# quadcopter.net
KiCad netlist of a schematic drawn in EAGLE
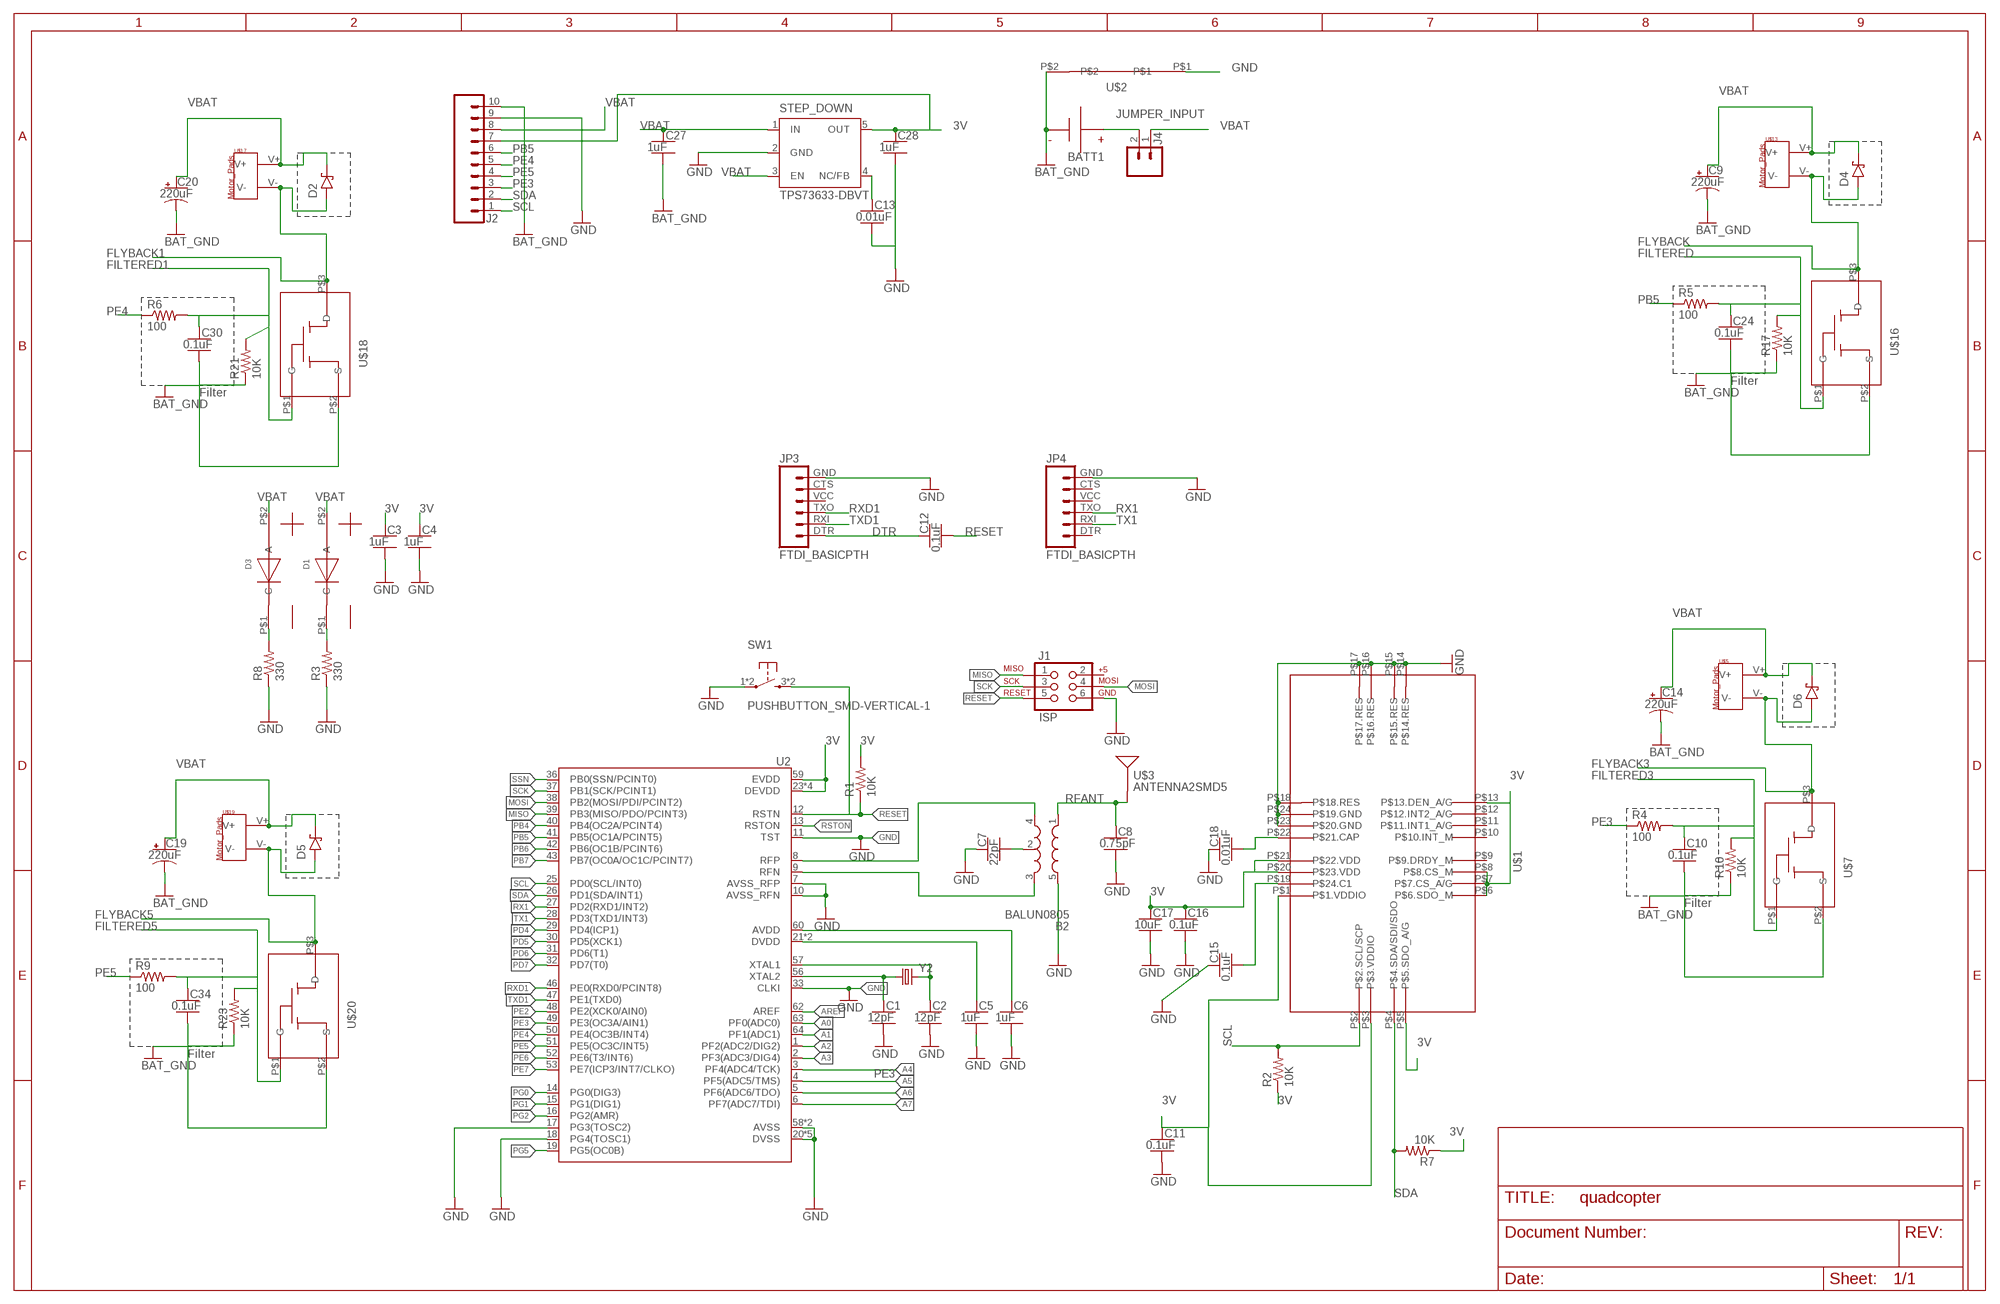
[diagram p0: schematic, sheet 1]

(export (version "E")
  (design (tool "Eeschema 10.0.6"))
  (components
    (comp (ref "B2")
      (value "BALUN0805")
      (footprint "eagle-import:BALUN")
      (fields (field (name "MFR") "Wurth Electronics Inc") (field (name "MPN") "748421245"))
      (libsource (lib "eagle-import") (part "BALUN0805"))
    )
    (comp (ref "BATT1")
      (value "BATTERY-HUBSAN-W/HOLDER")
      (footprint "eagle-import:BATTERY-W_HOLDER-380MAH-HUBSAN")
      (fields
        (field (name "MFR") "HUBSAN")
        (field (name "MPN") "X4-H107C-8-in-1")
        (field (name "CREATOR") "Swanson")
      )
      (libsource (lib "eagle-import") (part "BATTERY-HUBSAN-W/HOLDER"))
    )
    (comp (ref "C1")
      (value "12pF")
      (footprint "eagle-import:CAPC2012X140_HS")
      (fields
        (field (name "MFR") "Murata Electronics North America")
        (field (name "MPN") "GRM21A5C2E120JW01D")
      )
      (libsource (lib "eagle-import") (part "CAPACITOR-NP_SMD-2012-0805_CERAMIC-12PF"))
    )
    (comp (ref "C2")
      (value "12pF")
      (footprint "eagle-import:CAPC2012X140_HS")
      (fields
        (field (name "MFR") "Murata Electronics North America")
        (field (name "MPN") "GRM21A5C2E120JW01D")
      )
      (libsource (lib "eagle-import") (part "CAPACITOR-NP_SMD-2012-0805_CERAMIC-12PF"))
    )
    (comp (ref "C3")
      (value "1uF")
      (footprint "eagle-import:CAPC2012X140_HS")
      (fields
        (field (name "MFR") "Murata Electronics North America")
        (field (name "MPN") "GRM21BR71H105KA12L")
      )
      (libsource (lib "eagle-import") (part "CAPACITOR-NP_SMD-2012-0805_CERAMIC-1UF"))
    )
    (comp (ref "C4")
      (value "1uF")
      (footprint "eagle-import:CAPC2012X140_HS")
      (fields
        (field (name "MFR") "Murata Electronics North America")
        (field (name "MPN") "GRM21BR71H105KA12L")
      )
      (libsource (lib "eagle-import") (part "CAPACITOR-NP_SMD-2012-0805_CERAMIC-1UF"))
    )
    (comp (ref "C5")
      (value "1uF")
      (footprint "eagle-import:CAPC2012X140_HS")
      (fields
        (field (name "MFR") "Murata Electronics North America")
        (field (name "MPN") "GRM21BR71H105KA12L")
      )
      (libsource (lib "eagle-import") (part "CAPACITOR-NP_SMD-2012-0805_CERAMIC-1UF"))
    )
    (comp (ref "C6")
      (value "1uF")
      (footprint "eagle-import:CAPC2012X140_HS")
      (fields
        (field (name "MFR") "Murata Electronics North America")
        (field (name "MPN") "GRM21BR71H105KA12L")
      )
      (libsource (lib "eagle-import") (part "CAPACITOR-NP_SMD-2012-0805_CERAMIC-1UF"))
    )
    (comp (ref "C7")
      (value "22pF")
      (footprint "eagle-import:CAPC2012X140_HS")
      (fields
        (field (name "MFR") "Murata Electronics North America")
        (field (name "MPN") "GRM21A5C2E220JW01D")
      )
      (libsource (lib "eagle-import") (part "CAPACITOR-NP_SMD-2012-0805_CERAMIC-22PF"))
    )
    (comp (ref "C8")
      (value "0.75pF")
      (footprint "eagle-import:CAPC2012X140_HS")
      (fields
        (field (name "MFR") "Murata Electronics North America")
        (field (name "MPN") "GQM2195C2AR75CB01D")
      )
      (libsource (lib "eagle-import") (part "CAPACITOR-NP_SMD-2012-0805_CERAMIC-0.75PF"))
    )
    (comp (ref "C9")
      (value "220uF")
      (footprint "eagle-import:CAPMP7343X310_HS")
      (fields (field (name "MFR") "AVX Corporation") (field (name "MPN") "TAJD227K006RNJ"))
      (libsource (lib "eagle-import") (part "CAPACITOR-POL_SMD-7043-D_TANTALUM-220UF"))
    )
    (comp (ref "C10")
      (value "0.1uF")
      (footprint "eagle-import:CAPC2012X140_HS")
      (fields
        (field (name "MFR") "Murata Electronics North America")
        (field (name "MPN") "GRM21BR71H104KA01L")
      )
      (libsource (lib "eagle-import") (part "CAPACITOR-NP_SMD-2012-0805_CERAMIC-0.1UF"))
    )
    (comp (ref "C11")
      (value "0.1uF")
      (footprint "eagle-import:CAPC2012X140_HS")
      (fields
        (field (name "MFR") "Murata Electronics North America")
        (field (name "MPN") "GRM21BR71H104KA01L")
      )
      (libsource (lib "eagle-import") (part "CAPACITOR-NP_SMD-2012-0805_CERAMIC-0.1UF"))
    )
    (comp (ref "C12")
      (value "0.1uF")
      (footprint "eagle-import:CAPC2012X140_HS")
      (fields
        (field (name "MFR") "Murata Electronics North America")
        (field (name "MPN") "GRM21BR71H104KA01L")
      )
      (libsource (lib "eagle-import") (part "CAPACITOR-NP_SMD-2012-0805_CERAMIC-0.1UF"))
    )
    (comp (ref "C13")
      (value "0.01uF")
      (footprint "eagle-import:CAPC2012X140_HS")
      (fields
        (field (name "MFR") "Murata Electronics North America")
        (field (name "MPN") "GRM2195C1H103FA01D")
      )
      (libsource (lib "eagle-import") (part "CAPACITOR-NP_SMD-2012-0805_CERAMIC-0.01UF"))
    )
    (comp (ref "C14")
      (value "220uF")
      (footprint "eagle-import:CAPMP7343X310_HS")
      (fields (field (name "MFR") "AVX Corporation") (field (name "MPN") "TAJD227K006RNJ"))
      (libsource (lib "eagle-import") (part "CAPACITOR-POL_SMD-7043-D_TANTALUM-220UF"))
    )
    (comp (ref "C15")
      (value "0.1uF")
      (footprint "eagle-import:CAPC2012X140_HS")
      (fields
        (field (name "MFR") "Murata Electronics North America")
        (field (name "MPN") "GRM21BR71H104KA01L")
      )
      (libsource (lib "eagle-import") (part "CAPACITOR-NP_SMD-2012-0805_CERAMIC-0.1UF"))
    )
    (comp (ref "C16")
      (value "0.1uF")
      (footprint "eagle-import:CAPC2012X140_HS")
      (fields
        (field (name "MFR") "Murata Electronics North America")
        (field (name "MPN") "GRM21BR71H104KA01L")
      )
      (libsource (lib "eagle-import") (part "CAPACITOR-NP_SMD-2012-0805_CERAMIC-0.1UF"))
    )
    (comp (ref "C17")
      (value "10uF")
      (footprint "eagle-import:CAPC2012X140_HS")
      (fields
        (field (name "MFR") "Murata Electronics North America")
        (field (name "MPN") "GRM21BR61E106KA73L")
      )
      (libsource (lib "eagle-import") (part "CAPACITOR-NP_SMD-2012-0805_CERAMIC-10UF"))
    )
    (comp (ref "C18")
      (value "0.01uF")
      (footprint "eagle-import:CAPC2012X140_HS")
      (fields
        (field (name "MFR") "Murata Electronics North America")
        (field (name "MPN") "GRM2195C1H103FA01D")
      )
      (libsource (lib "eagle-import") (part "CAPACITOR-NP_SMD-2012-0805_CERAMIC-0.01UF"))
    )
    (comp (ref "C19")
      (value "220uF")
      (footprint "eagle-import:CAPMP7343X310_HS")
      (fields (field (name "MFR") "AVX Corporation") (field (name "MPN") "TAJD227K006RNJ"))
      (libsource (lib "eagle-import") (part "CAPACITOR-POL_SMD-7043-D_TANTALUM-220UF"))
    )
    (comp (ref "C20")
      (value "220uF")
      (footprint "eagle-import:CAPMP7343X310_HS")
      (fields (field (name "MFR") "AVX Corporation") (field (name "MPN") "TAJD227K006RNJ"))
      (libsource (lib "eagle-import") (part "CAPACITOR-POL_SMD-7043-D_TANTALUM-220UF"))
    )
    (comp (ref "C24")
      (value "0.1uF")
      (footprint "eagle-import:CAPC2012X140_HS")
      (fields
        (field (name "MFR") "Murata Electronics North America")
        (field (name "MPN") "GRM21BR71H104KA01L")
      )
      (libsource (lib "eagle-import") (part "CAPACITOR-NP_SMD-2012-0805_CERAMIC-0.1UF"))
    )
    (comp (ref "C27")
      (value "1uF")
      (footprint "eagle-import:CAPC2012X140_HS")
      (fields
        (field (name "MFR") "Murata Electronics North America")
        (field (name "MPN") "GRM21BR71H105KA12L")
      )
      (libsource (lib "eagle-import") (part "CAPACITOR-NP_SMD-2012-0805_CERAMIC-1UF"))
    )
    (comp (ref "C28")
      (value "1uF")
      (footprint "eagle-import:CAPC2012X140_HS")
      (fields
        (field (name "MFR") "Murata Electronics North America")
        (field (name "MPN") "GRM21BR71H105KA12L")
      )
      (libsource (lib "eagle-import") (part "CAPACITOR-NP_SMD-2012-0805_CERAMIC-1UF"))
    )
    (comp (ref "C30")
      (value "0.1uF")
      (footprint "eagle-import:CAPC2012X140_HS")
      (fields
        (field (name "MFR") "Murata Electronics North America")
        (field (name "MPN") "GRM21BR71H104KA01L")
      )
      (libsource (lib "eagle-import") (part "CAPACITOR-NP_SMD-2012-0805_CERAMIC-0.1UF"))
    )
    (comp (ref "C34")
      (value "0.1uF")
      (footprint "eagle-import:CAPC2012X140_HS")
      (fields
        (field (name "MFR") "Murata Electronics North America")
        (field (name "MPN") "GRM21BR71H104KA01L")
      )
      (libsource (lib "eagle-import") (part "CAPACITOR-NP_SMD-2012-0805_CERAMIC-0.1UF"))
    )
    (comp (ref "D1")
      (value "LED-RED")
      (footprint "eagle-import:RED_LED")
      (fields
        (field (name "MFR") "Lite-On Inc ")
        (field (name "MPN") "LTST-C170EKT ")
        (field (name "CREATOR") "Michael Bagherpour")
        (field (name "REVIEWER") "group 4")
      )
      (libsource (lib "eagle-import") (part "LED-RED"))
    )
    (comp (ref "D2")
      (value "DIODE-SCHOTTKY_SMD-SOD123")
      (footprint "eagle-import:SOD3716X135_HS")
      (libsource (lib "eagle-import") (part "DIODE-SCHOTTKY_SMD-SOD123"))
    )
    (comp (ref "D3")
      (value "LED-RED")
      (footprint "eagle-import:RED_LED")
      (fields
        (field (name "MFR") "Lite-On Inc ")
        (field (name "MPN") "LTST-C170EKT ")
        (field (name "CREATOR") "Michael Bagherpour")
        (field (name "REVIEWER") "group 4")
      )
      (libsource (lib "eagle-import") (part "LED-RED"))
    )
    (comp (ref "D4")
      (value "DIODE-SCHOTTKY_SMD-SOD123")
      (footprint "eagle-import:SOD3716X135_HS")
      (libsource (lib "eagle-import") (part "DIODE-SCHOTTKY_SMD-SOD123"))
    )
    (comp (ref "D5")
      (value "DIODE-SCHOTTKY_SMD-SOD123")
      (footprint "eagle-import:SOD3716X135_HS")
      (libsource (lib "eagle-import") (part "DIODE-SCHOTTKY_SMD-SOD123"))
    )
    (comp (ref "D6")
      (value "DIODE-SCHOTTKY_SMD-SOD123")
      (footprint "eagle-import:SOD3716X135_HS")
      (libsource (lib "eagle-import") (part "DIODE-SCHOTTKY_SMD-SOD123"))
    )
    (comp (ref "J1")
      (value "ISP")
      (footprint "eagle-import:2X3-NS")
      (fields (field (name "MFR") "Amphenol FCI") (field (name "MPN") "67997-206HLF"))
      (libsource (lib "eagle-import") (part "AVR_SPI_PRG_6NS"))
    )
    (comp (ref "J2")
      (value "SIP-10_TH-254X10-1")
      (footprint "eagle-import:HDRV10W63P254_10X1_2540X254H838_HS")
      (fields (field (name "MFR") "Amphenol FCI") (field (name "MPN") "68000-110HLF"))
      (libsource (lib "eagle-import") (part "SIP-10_TH-254X10-1"))
    )
    (comp (ref "J4")
      (value "MALE_HEADER_2POS-2X1-0.1IN")
      (footprint "eagle-import:MALE_HEADER_2X1_0.1IN")
      (fields
        (field (name "MFR") "3M")
        (field (name "MPN") "961102-6404-AR")
        (field (name "CREATOR") "SWANSON")
        (field (name "REVIEWER") "group 4")
      )
      (libsource (lib "eagle-import") (part "MALE_HEADER_2POS-2X1-0.1IN"))
    )
    (comp (ref "JP3")
      (value "FTDI_BASICPTH")
      (footprint "eagle-import:FTDI_BASIC")
      (fields (field (name "MFR") "Amphenol FCI") (field (name "MPN") "68016-406HLF"))
      (libsource (lib "eagle-import") (part "FTDI_BASICPTH"))
    )
    (comp (ref "JP4")
      (value "FTDI_BASICPTH")
      (footprint "eagle-import:FTDI_BASIC")
      (fields (field (name "MFR") "Amphenol FCI") (field (name "MPN") "68016-406HLF"))
      (libsource (lib "eagle-import") (part "FTDI_BASICPTH"))
    )
    (comp (ref "R1")
      (value "10K")
      (footprint "eagle-import:RESC2012X60_HS")
      (fields (field (name "MFR") "Yageo") (field (name "MPN") "RC0805JR-0710KL"))
      (libsource (lib "eagle-import") (part "RESISTOR_SMD-2012-0805-10K"))
    )
    (comp (ref "R2")
      (value "10K")
      (footprint "eagle-import:RESC2012X60_HS")
      (fields (field (name "MFR") "Yageo") (field (name "MPN") "RC0805JR-0710KL"))
      (libsource (lib "eagle-import") (part "RESISTOR_SMD-2012-0805-10K"))
    )
    (comp (ref "R3")
      (value "330")
      (footprint "eagle-import:RESC2012X60_HS")
      (fields (field (name "MFR") "Yageo") (field (name "MPN") "RC0805JR-07330RL"))
      (libsource (lib "eagle-import") (part "RESISTOR_SMD-2012-0805-330"))
    )
    (comp (ref "R4")
      (value "100")
      (footprint "eagle-import:RESC2012X60_HS")
      (fields (field (name "MFR") "Yageo") (field (name "MPN") "RC0805JR-07100RL"))
      (libsource (lib "eagle-import") (part "RESISTOR_SMD-2012-0805-100"))
    )
    (comp (ref "R5")
      (value "100")
      (footprint "eagle-import:RESC2012X60_HS")
      (fields (field (name "MFR") "Yageo") (field (name "MPN") "RC0805JR-07100RL"))
      (libsource (lib "eagle-import") (part "RESISTOR_SMD-2012-0805-100"))
    )
    (comp (ref "R6")
      (value "100")
      (footprint "eagle-import:RESC2012X60_HS")
      (fields (field (name "MFR") "Yageo") (field (name "MPN") "RC0805JR-07100RL"))
      (libsource (lib "eagle-import") (part "RESISTOR_SMD-2012-0805-100"))
    )
    (comp (ref "R7")
      (value "10K")
      (footprint "eagle-import:RESC2012X60_HS")
      (fields (field (name "MFR") "Yageo") (field (name "MPN") "RC0805JR-0710KL"))
      (libsource (lib "eagle-import") (part "RESISTOR_SMD-2012-0805-10K"))
    )
    (comp (ref "R8")
      (value "330")
      (footprint "eagle-import:RESC2012X60_HS")
      (fields (field (name "MFR") "Yageo") (field (name "MPN") "RC0805JR-07330RL"))
      (libsource (lib "eagle-import") (part "RESISTOR_SMD-2012-0805-330"))
    )
    (comp (ref "R9")
      (value "100")
      (footprint "eagle-import:RESC2012X60_HS")
      (fields (field (name "MFR") "Yageo") (field (name "MPN") "RC0805JR-07100RL"))
      (libsource (lib "eagle-import") (part "RESISTOR_SMD-2012-0805-100"))
    )
    (comp (ref "R10")
      (value "10K")
      (footprint "eagle-import:RESC2012X60_HS")
      (fields (field (name "MFR") "Yageo") (field (name "MPN") "RC0805JR-0710KL"))
      (libsource (lib "eagle-import") (part "RESISTOR_SMD-2012-0805-10K"))
    )
    (comp (ref "R17")
      (value "10K")
      (footprint "eagle-import:RESC2012X60_HS")
      (fields (field (name "MFR") "Yageo") (field (name "MPN") "RC0805JR-0710KL"))
      (libsource (lib "eagle-import") (part "RESISTOR_SMD-2012-0805-10K"))
    )
    (comp (ref "R21")
      (value "10K")
      (footprint "eagle-import:RESC2012X60_HS")
      (fields (field (name "MFR") "Yageo") (field (name "MPN") "RC0805JR-0710KL"))
      (libsource (lib "eagle-import") (part "RESISTOR_SMD-2012-0805-10K"))
    )
    (comp (ref "R23")
      (value "10K")
      (footprint "eagle-import:RESC2012X60_HS")
      (fields (field (name "MFR") "Yageo") (field (name "MPN") "RC0805JR-0710KL"))
      (libsource (lib "eagle-import") (part "RESISTOR_SMD-2012-0805-10K"))
    )
    (comp (ref "STEP_DOWN")
      (value "TPS73633-DBVT")
      (footprint "eagle-import:SOT23-DBV")
      (fields (field (name "MFR") "Texas Instruments") (field (name "MPN") "LP3985IM5X-3.0/NOPB"))
      (libsource (lib "eagle-import") (part "TPS73633-DBVT"))
    )
    (comp (ref "SW1")
      (value "PUSHBUTTON_SMD-VERTICAL-1")
      (footprint "eagle-import:TE_FSM8JSMA_HS")
      (fields (field (name "MFR") "TE Connectivity Alcoswitch Switches") (field (name "MPN") "FSM4JSMA"))
      (libsource (lib "eagle-import") (part "PUSHBUTTON_SMD-VERTICAL-1"))
    )
    (comp (ref "U$1")
      (value "LSM9DS1TR_IMU-9_AXIS")
      (footprint "eagle-import:IMU")
      (fields
        (field (name "MFR") "STMicroelectronics ")
        (field (name "MPN") "LSM9DS1TR ")
        (field (name "CREATOR") "Michael Bagherpour")
        (field (name "REVIEWER") "group 4")
      )
      (libsource (lib "eagle-import") (part "LSM9DS1TR_IMU-9_AXIS"))
    )
    (comp (ref "U$2")
      (value "NET_BRIDGE")
      (footprint "eagle-import:NET_BRIDGE")
      (fields
        (field (name "MFR") "none")
        (field (name "CREATOR") "Michael")
        (field (name "REVIEWER") "group 4")
      )
      (libsource (lib "eagle-import") (part "NET_BRIDGE"))
    )
    (comp (ref "U$3")
      (value "ANTENNA2SMD5")
      (footprint "eagle-import:ANTENNA-CHIP5")
      (fields (field (name "MFR") "Linx Technologies Inc.") (field (name "MPN") "ANT-2.45-CHP-T"))
      (libsource (lib "eagle-import") (part "ANTENNA2SMD5"))
    )
    (comp (ref "U$5")
      (value "MOTOR_PADS")
      (footprint "eagle-import:MOTOR_PADS")
      (fields (field (name "MFR") "NA"))
      (libsource (lib "eagle-import") (part "MOTOR_PADS"))
    )
    (comp (ref "U$7")
      (value "MOSFET-N_CHANNEL")
      (footprint "eagle-import:MOSFET")
      (fields
        (field (name "MFR") "Vishay Siliconix ")
        (field (name "MPN") "SI2302CDS-T1-E3 ")
        (field (name "CREATOR") "Michael Bagherpour")
        (field (name "REVIEWER") "group 4")
      )
      (libsource (lib "eagle-import") (part "MOSFET-N_CHANNEL"))
    )
    (comp (ref "U$13")
      (value "MOTOR_PADS")
      (footprint "eagle-import:MOTOR_PADS")
      (fields (field (name "MFR") "NA"))
      (libsource (lib "eagle-import") (part "MOTOR_PADS"))
    )
    (comp (ref "U$16")
      (value "MOSFET-N_CHANNEL")
      (footprint "eagle-import:MOSFET")
      (fields
        (field (name "MFR") "Vishay Siliconix ")
        (field (name "MPN") "SI2302CDS-T1-E3 ")
        (field (name "CREATOR") "Michael Bagherpour")
        (field (name "REVIEWER") "group 4")
      )
      (libsource (lib "eagle-import") (part "MOSFET-N_CHANNEL"))
    )
    (comp (ref "U$17")
      (value "MOTOR_PADS")
      (footprint "eagle-import:MOTOR_PADS")
      (fields (field (name "MFR") "NA"))
      (libsource (lib "eagle-import") (part "MOTOR_PADS"))
    )
    (comp (ref "U$18")
      (value "MOSFET-N_CHANNEL")
      (footprint "eagle-import:MOSFET")
      (fields
        (field (name "MFR") "Vishay Siliconix ")
        (field (name "MPN") "SI2302CDS-T1-E3 ")
        (field (name "CREATOR") "Michael Bagherpour")
        (field (name "REVIEWER") "group 4")
      )
      (libsource (lib "eagle-import") (part "MOSFET-N_CHANNEL"))
    )
    (comp (ref "U$19")
      (value "MOTOR_PADS")
      (footprint "eagle-import:MOTOR_PADS")
      (fields (field (name "MFR") "NA"))
      (libsource (lib "eagle-import") (part "MOTOR_PADS"))
    )
    (comp (ref "U$20")
      (value "MOSFET-N_CHANNEL")
      (footprint "eagle-import:MOSFET")
      (fields
        (field (name "MFR") "Vishay Siliconix ")
        (field (name "MPN") "SI2302CDS-T1-E3 ")
        (field (name "CREATOR") "Michael Bagherpour")
        (field (name "REVIEWER") "group 4")
      )
      (libsource (lib "eagle-import") (part "MOSFET-N_CHANNEL"))
    )
    (comp (ref "U2")
      (value "ATMEGA128RFA1")
      (footprint "eagle-import:QFN-64")
      (fields
        (field (name "MFR") "Atmel")
        (field (name "MPN") "ATMEGA128RFA1-ZUR00")
        (field (name "CREATOR") "Swanson")
      )
      (libsource (lib "eagle-import") (part "ATMEGA128RFA1"))
    )
    (comp (ref "Y2")
      (value "CRYSTAL5X3")
      (footprint "eagle-import:CRYSTAL-SMD-5X3")
      (fields (field (name "MFR") "Abracon LLC") (field (name "MPN") "ABM3B-16.000MHZ-B2-T"))
      (libsource (lib "eagle-import") (part "CRYSTAL5X3"))
    )
  )
  (nets
    (net (code "1") (name "/3V") (class "Default")
      (node (ref "C11") (pin "1") (pinfunction "1_1") (pintype "passive"))
      (node (ref "C16") (pin "1") (pinfunction "1_1") (pintype "passive"))
      (node (ref "C17") (pin "1") (pinfunction "1_1") (pintype "passive"))
      (node (ref "C28") (pin "1") (pinfunction "1_1") (pintype "passive"))
      (node (ref "C3") (pin "1") (pinfunction "1_1") (pintype "passive"))
      (node (ref "C4") (pin "1") (pinfunction "1_1") (pintype "passive"))
      (node (ref "J2") (pin "7") (pinfunction "7_7") (pintype "passive"))
      (node (ref "R1") (pin "2") (pinfunction "2_2") (pintype "passive"))
      (node (ref "R2") (pin "1") (pinfunction "1_1") (pintype "passive"))
      (node (ref "R7") (pin "1") (pinfunction "1_1") (pintype "passive"))
      (node (ref "STEP_DOWN") (pin "5") (pinfunction "OUT_5") (pintype "passive"))
      (node (ref "U$1") (pin "P$1") (pinfunction "P$1.VDDIO_P$1") (pintype "bidirectional"))
      (node (ref "U$1") (pin "P$13") (pinfunction "P$13.DEN_A/G_P$13") (pintype "bidirectional"))
      (node (ref "U$1") (pin "P$20") (pinfunction "P$23.VDD_P$20") (pintype "bidirectional"))
      (node (ref "U$1") (pin "P$21") (pinfunction "P$22.VDD_P$21") (pintype "bidirectional"))
      (node (ref "U$1") (pin "P$3") (pinfunction "P$3.VDDIO_P$3") (pintype "bidirectional"))
      (node (ref "U$1") (pin "P$5") (pinfunction "P$5.SDO_A/G_P$5") (pintype "bidirectional"))
      (node (ref "U$1") (pin "P$6") (pinfunction "P$6.SDO_M_P$6") (pintype "bidirectional"))
      (node (ref "U$1") (pin "P$7") (pinfunction "P$7.CS_A/G_P$7") (pintype "bidirectional"))
      (node (ref "U$1") (pin "P$8") (pinfunction "P$8.CS_M_P$8") (pintype "bidirectional"))
      (node (ref "U2") (pin "23") (pinfunction "DEVDD_23") (pintype "bidirectional"))
      (node (ref "U2") (pin "34") (pinfunction "DEVDD_34") (pintype "bidirectional"))
      (node (ref "U2") (pin "44") (pinfunction "DEVDD_44") (pintype "bidirectional"))
      (node (ref "U2") (pin "54") (pinfunction "DEVDD_54") (pintype "bidirectional"))
      (node (ref "U2") (pin "59") (pinfunction "EVDD_59") (pintype "bidirectional"))
    )
    (net (code "2") (name "/DTR") (class "Default")
      (node (ref "C12") (pin "1") (pinfunction "1_1") (pintype "passive"))
      (node (ref "JP3") (pin "DTR") (pinfunction "1_DTR") (pintype "passive"))
    )
    (net (code "3") (name "/FILTERED") (class "Default")
      (node (ref "C24") (pin "1") (pinfunction "1_1") (pintype "passive"))
      (node (ref "R17") (pin "2") (pinfunction "2_2") (pintype "passive"))
      (node (ref "R5") (pin "2") (pinfunction "2_2") (pintype "passive"))
      (node (ref "U$16") (pin "P$1") (pinfunction "G_P$1") (pintype "bidirectional"))
    )
    (net (code "4") (name "/FILTERED1") (class "Default")
      (node (ref "C30") (pin "1") (pinfunction "1_1") (pintype "passive"))
      (node (ref "R21") (pin "2") (pinfunction "2_2") (pintype "passive"))
      (node (ref "R6") (pin "2") (pinfunction "2_2") (pintype "passive"))
      (node (ref "U$18") (pin "P$1") (pinfunction "G_P$1") (pintype "bidirectional"))
    )
    (net (code "5") (name "/FILTERED3") (class "Default")
      (node (ref "C10") (pin "1") (pinfunction "1_1") (pintype "passive"))
      (node (ref "R10") (pin "2") (pinfunction "2_2") (pintype "passive"))
      (node (ref "R4") (pin "2") (pinfunction "2_2") (pintype "passive"))
      (node (ref "U$7") (pin "P$1") (pinfunction "G_P$1") (pintype "bidirectional"))
    )
    (net (code "6") (name "/FILTERED5") (class "Default")
      (node (ref "C34") (pin "1") (pinfunction "1_1") (pintype "passive"))
      (node (ref "R23") (pin "2") (pinfunction "2_2") (pintype "passive"))
      (node (ref "R9") (pin "2") (pinfunction "2_2") (pintype "passive"))
      (node (ref "U$20") (pin "P$1") (pinfunction "G_P$1") (pintype "bidirectional"))
    )
    (net (code "7") (name "/FLYBACK") (class "Default")
      (node (ref "D4") (pin "A") (pinfunction "A_A") (pintype "passive"))
      (node (ref "U$13") (pin "V-") (pinfunction "V-_V-") (pintype "bidirectional"))
      (node (ref "U$16") (pin "P$3") (pinfunction "D_P$3") (pintype "bidirectional"))
    )
    (net (code "8") (name "/FLYBACK1") (class "Default")
      (node (ref "D2") (pin "A") (pinfunction "A_A") (pintype "passive"))
      (node (ref "U$17") (pin "V-") (pinfunction "V-_V-") (pintype "bidirectional"))
      (node (ref "U$18") (pin "P$3") (pinfunction "D_P$3") (pintype "bidirectional"))
    )
    (net (code "9") (name "/FLYBACK3") (class "Default")
      (node (ref "D6") (pin "A") (pinfunction "A_A") (pintype "passive"))
      (node (ref "U$5") (pin "V-") (pinfunction "V-_V-") (pintype "bidirectional"))
      (node (ref "U$7") (pin "P$3") (pinfunction "D_P$3") (pintype "bidirectional"))
    )
    (net (code "10") (name "/FLYBACK5") (class "Default")
      (node (ref "D5") (pin "A") (pinfunction "A_A") (pintype "passive"))
      (node (ref "U$19") (pin "V-") (pinfunction "V-_V-") (pintype "bidirectional"))
      (node (ref "U$20") (pin "P$3") (pinfunction "D_P$3") (pintype "bidirectional"))
    )
    (net (code "11") (name "/JUMPER_INPUT") (class "Default")
      (node (ref "BATT1") (pin "+") (pinfunction "P_+") (pintype "bidirectional"))
      (node (ref "J4") (pin "2") (pinfunction "2_2") (pintype "passive"))
    )
    (net (code "12") (name "/RFANT") (class "Default")
      (node (ref "B2") (pin "1") (pinfunction "IN_1") (pintype "bidirectional"))
      (node (ref "C8") (pin "1") (pinfunction "1_1") (pintype "passive"))
      (node (ref "U$3") (pin "FEED") (pinfunction "SIGNAL_FEED") (pintype "bidirectional"))
    )
    (net (code "13") (name "/VBAT") (class "Default")
      (node (ref "C14") (pin "1") (pinfunction "+_1") (pintype "passive"))
      (node (ref "C19") (pin "1") (pinfunction "+_1") (pintype "passive"))
      (node (ref "C20") (pin "1") (pinfunction "+_1") (pintype "passive"))
      (node (ref "C27") (pin "1") (pinfunction "1_1") (pintype "passive"))
      (node (ref "C9") (pin "1") (pinfunction "+_1") (pintype "passive"))
      (node (ref "D1") (pin "P$2") (pinfunction "A_P$2") (pintype "bidirectional"))
      (node (ref "D2") (pin "C") (pinfunction "C_C") (pintype "passive"))
      (node (ref "D3") (pin "P$2") (pinfunction "A_P$2") (pintype "bidirectional"))
      (node (ref "D4") (pin "C") (pinfunction "C_C") (pintype "passive"))
      (node (ref "D5") (pin "C") (pinfunction "C_C") (pintype "passive"))
      (node (ref "D6") (pin "C") (pinfunction "C_C") (pintype "passive"))
      (node (ref "J2") (pin "8") (pinfunction "8_8") (pintype "passive"))
      (node (ref "J4") (pin "1") (pinfunction "1_1") (pintype "passive"))
      (node (ref "STEP_DOWN") (pin "1") (pinfunction "IN_1") (pintype "input"))
      (node (ref "STEP_DOWN") (pin "3") (pinfunction "EN_3") (pintype "input"))
      (node (ref "U$13") (pin "V+") (pinfunction "V+_V+") (pintype "bidirectional"))
      (node (ref "U$17") (pin "V+") (pinfunction "V+_V+") (pintype "bidirectional"))
      (node (ref "U$19") (pin "V+") (pinfunction "V+_V+") (pintype "bidirectional"))
      (node (ref "U$5") (pin "V+") (pinfunction "V+_V+") (pintype "bidirectional"))
    )
    (net (code "14") (name "A0") (class "Default")
      (node (ref "U2") (pin "63") (pinfunction "PF0(ADC0)_63") (pintype "bidirectional"))
    )
    (net (code "15") (name "A1") (class "Default")
      (node (ref "U2") (pin "64") (pinfunction "PF1(ADC1)_64") (pintype "bidirectional"))
    )
    (net (code "16") (name "A2") (class "Default")
      (node (ref "U2") (pin "1") (pinfunction "PF2(ADC2/DIG2)_1") (pintype "bidirectional"))
    )
    (net (code "17") (name "A3") (class "Default")
      (node (ref "U2") (pin "2") (pinfunction "PF3(ADC3/DIG4)_2") (pintype "bidirectional"))
    )
    (net (code "18") (name "A4") (class "Default")
      (node (ref "U2") (pin "3") (pinfunction "PF4(ADC4/TCK)_3") (pintype "bidirectional"))
    )
    (net (code "19") (name "A5") (class "Default")
      (node (ref "U2") (pin "4") (pinfunction "PF5(ADC5/TMS)_4") (pintype "bidirectional"))
    )
    (net (code "20") (name "A6") (class "Default")
      (node (ref "U2") (pin "5") (pinfunction "PF6(ADC6/TDO)_5") (pintype "bidirectional"))
    )
    (net (code "21") (name "A7") (class "Default")
      (node (ref "U2") (pin "6") (pinfunction "PF7(ADC7/TDI)_6") (pintype "bidirectional"))
    )
    (net (code "22") (name "AREF") (class "Default")
      (node (ref "U2") (pin "62") (pinfunction "AREF_62") (pintype "bidirectional"))
    )
    (net (code "23") (name "BAT_GND") (class "Default")
      (node (ref "BATT1") (pin "-") (pinfunction "N_-") (pintype "bidirectional"))
      (node (ref "C10") (pin "2") (pinfunction "2_2") (pintype "passive"))
      (node (ref "C14") (pin "2") (pinfunction "-_2") (pintype "passive"))
      (node (ref "C19") (pin "2") (pinfunction "-_2") (pintype "passive"))
      (node (ref "C20") (pin "2") (pinfunction "-_2") (pintype "passive"))
      (node (ref "C24") (pin "2") (pinfunction "2_2") (pintype "passive"))
      (node (ref "C27") (pin "2") (pinfunction "2_2") (pintype "passive"))
      (node (ref "C30") (pin "2") (pinfunction "2_2") (pintype "passive"))
      (node (ref "C34") (pin "2") (pinfunction "2_2") (pintype "passive"))
      (node (ref "C9") (pin "2") (pinfunction "-_2") (pintype "passive"))
      (node (ref "J2") (pin "10") (pinfunction "10_10") (pintype "passive"))
      (node (ref "R10") (pin "1") (pinfunction "1_1") (pintype "passive"))
      (node (ref "R17") (pin "1") (pinfunction "1_1") (pintype "passive"))
      (node (ref "R21") (pin "1") (pinfunction "1_1") (pintype "passive"))
      (node (ref "R23") (pin "1") (pinfunction "1_1") (pintype "passive"))
      (node (ref "U$16") (pin "P$2") (pinfunction "S_P$2") (pintype "bidirectional"))
      (node (ref "U$18") (pin "P$2") (pinfunction "S_P$2") (pintype "bidirectional"))
      (node (ref "U$2") (pin "P$2") (pinfunction "P$2_P$2") (pintype "bidirectional"))
      (node (ref "U$20") (pin "P$2") (pinfunction "S_P$2") (pintype "bidirectional"))
      (node (ref "U$7") (pin "P$2") (pinfunction "S_P$2") (pintype "bidirectional"))
    )
    (net (code "24") (name "GND") (class "Default")
      (node (ref "B2") (pin "5") (pinfunction "GND_5") (pintype "bidirectional"))
      (node (ref "C1") (pin "2") (pinfunction "2_2") (pintype "passive"))
      (node (ref "C11") (pin "2") (pinfunction "2_2") (pintype "passive"))
      (node (ref "C13") (pin "2") (pinfunction "2_2") (pintype "passive"))
      (node (ref "C15") (pin "1") (pinfunction "1_1") (pintype "passive"))
      (node (ref "C16") (pin "2") (pinfunction "2_2") (pintype "passive"))
      (node (ref "C17") (pin "2") (pinfunction "2_2") (pintype "passive"))
      (node (ref "C18") (pin "1") (pinfunction "1_1") (pintype "passive"))
      (node (ref "C2") (pin "2") (pinfunction "2_2") (pintype "passive"))
      (node (ref "C28") (pin "2") (pinfunction "2_2") (pintype "passive"))
      (node (ref "C3") (pin "2") (pinfunction "2_2") (pintype "passive"))
      (node (ref "C4") (pin "2") (pinfunction "2_2") (pintype "passive"))
      (node (ref "C5") (pin "2") (pinfunction "2_2") (pintype "passive"))
      (node (ref "C6") (pin "2") (pinfunction "2_2") (pintype "passive"))
      (node (ref "C7") (pin "1") (pinfunction "1_1") (pintype "passive"))
      (node (ref "C8") (pin "2") (pinfunction "2_2") (pintype "passive"))
      (node (ref "J1") (pin "6") (pinfunction "6_6") (pintype "passive"))
      (node (ref "J2") (pin "9") (pinfunction "9_9") (pintype "passive"))
      (node (ref "JP3") (pin "GND") (pinfunction "6_GND") (pintype "passive"))
      (node (ref "JP4") (pin "GND") (pinfunction "6_GND") (pintype "passive"))
      (node (ref "R3") (pin "1") (pinfunction "1_1") (pintype "passive"))
      (node (ref "R8") (pin "1") (pinfunction "1_1") (pintype "passive"))
      (node (ref "STEP_DOWN") (pin "2") (pinfunction "GND_2") (pintype "input"))
      (node (ref "SW1") (pin "1") (pinfunction "1_1") (pintype "passive"))
      (node (ref "SW1") (pin "2") (pinfunction "1_2") (pintype "passive"))
      (node (ref "U$1") (pin "P$14") (pinfunction "P$14.RES_P$14") (pintype "bidirectional"))
      (node (ref "U$1") (pin "P$15") (pinfunction "P$15.RES_P$15") (pintype "bidirectional"))
      (node (ref "U$1") (pin "P$16") (pinfunction "P$16.RES_P$16") (pintype "bidirectional"))
      (node (ref "U$1") (pin "P$17") (pinfunction "P$17.RES_P$17") (pintype "bidirectional"))
      (node (ref "U$1") (pin "P$18") (pinfunction "P$18.RES_P$18") (pintype "bidirectional"))
      (node (ref "U$1") (pin "P$23") (pinfunction "P$20.GND_P$23") (pintype "bidirectional"))
      (node (ref "U$1") (pin "P$24") (pinfunction "P$19.GND_P$24") (pintype "bidirectional"))
      (node (ref "U$2") (pin "P$1") (pinfunction "P$1_P$1") (pintype "bidirectional"))
      (node (ref "U2") (pin "10") (pinfunction "AVSS_RFN_10") (pintype "bidirectional"))
      (node (ref "U2") (pin "11") (pinfunction "TST_11") (pintype "bidirectional"))
      (node (ref "U2") (pin "17") (pinfunction "PG3(TOSC2)_17") (pintype "bidirectional"))
      (node (ref "U2") (pin "18") (pinfunction "PG4(TOSC1)_18") (pintype "bidirectional"))
      (node (ref "U2") (pin "20") (pinfunction "DVSS_20") (pintype "bidirectional"))
      (node (ref "U2") (pin "24") (pinfunction "DVSS_24") (pintype "bidirectional"))
      (node (ref "U2") (pin "33") (pinfunction "CLKI_33") (pintype "bidirectional"))
      (node (ref "U2") (pin "35") (pinfunction "DVSS_35") (pintype "bidirectional"))
      (node (ref "U2") (pin "45") (pinfunction "DVSS_45") (pintype "bidirectional"))
      (node (ref "U2") (pin "55") (pinfunction "DVSS_55") (pintype "bidirectional"))
      (node (ref "U2") (pin "58") (pinfunction "AVSS_58") (pintype "bidirectional"))
      (node (ref "U2") (pin "61") (pinfunction "AVSS_61") (pintype "bidirectional"))
      (node (ref "U2") (pin "7") (pinfunction "AVSS_RFP_7") (pintype "bidirectional"))
    )
    (net (code "25") (name "MISO") (class "Default")
      (node (ref "J1") (pin "1") (pinfunction "1_1") (pintype "passive"))
      (node (ref "U2") (pin "39") (pinfunction "PB3(MISO/PDO/PCINT3)_39") (pintype "bidirectional"))
    )
    (net (code "26") (name "MOSI") (class "Default")
      (node (ref "J1") (pin "4") (pinfunction "4_4") (pintype "passive"))
      (node (ref "U2") (pin "38") (pinfunction "PB2(MOSI/PDI/PCINT2)_38") (pintype "bidirectional"))
    )
    (net (code "27") (name "Net-(B2-GND-Pad2)") (class "Default")
      (node (ref "B2") (pin "2") (pinfunction "GND_2") (pintype "bidirectional"))
      (node (ref "C7") (pin "2") (pinfunction "2_2") (pintype "passive"))
    )
    (net (code "28") (name "Net-(B2-OUT1)") (class "Default")
      (node (ref "B2") (pin "4") (pinfunction "OUT1_4") (pintype "bidirectional"))
      (node (ref "U2") (pin "8") (pinfunction "RFP_8") (pintype "bidirectional"))
    )
    (net (code "29") (name "Net-(B2-OUT2)") (class "Default")
      (node (ref "B2") (pin "3") (pinfunction "OUT2_3") (pintype "bidirectional"))
      (node (ref "U2") (pin "9") (pinfunction "RFN_9") (pintype "bidirectional"))
    )
    (net (code "30") (name "Net-(C5-Pad1)") (class "Default")
      (node (ref "C5") (pin "1") (pinfunction "1_1") (pintype "passive"))
      (node (ref "U2") (pin "21") (pinfunction "DVDD_21") (pintype "bidirectional"))
      (node (ref "U2") (pin "22") (pinfunction "DVDD_22") (pintype "bidirectional"))
    )
    (net (code "31") (name "Net-(D1-C)") (class "Default")
      (node (ref "D1") (pin "P$1") (pinfunction "C_P$1") (pintype "bidirectional"))
      (node (ref "R3") (pin "2") (pinfunction "2_2") (pintype "passive"))
    )
    (net (code "32") (name "Net-(D3-C)") (class "Default")
      (node (ref "D3") (pin "P$1") (pinfunction "C_P$1") (pintype "bidirectional"))
      (node (ref "R8") (pin "2") (pinfunction "2_2") (pintype "passive"))
    )
    (net (code "33") (name "Net-(STEP_DOWN-NC{slash}FB)") (class "Default")
      (node (ref "C13") (pin "1") (pinfunction "1_1") (pintype "passive"))
      (node (ref "STEP_DOWN") (pin "4") (pinfunction "NC/FB_4") (pintype "passive"))
    )
    (net (code "34") (name "Net-(U$1-P$21.CAP)") (class "Default")
      (node (ref "C18") (pin "2") (pinfunction "2_2") (pintype "passive"))
      (node (ref "U$1") (pin "P$22") (pinfunction "P$21.CAP_P$22") (pintype "bidirectional"))
    )
    (net (code "35") (name "Net-(U$1-P$24.C1)") (class "Default")
      (node (ref "C15") (pin "2") (pinfunction "2_2") (pintype "passive"))
      (node (ref "U$1") (pin "P$19") (pinfunction "P$24.C1_P$19") (pintype "bidirectional"))
    )
    (net (code "36") (name "Net-(U2-AVDD)") (class "Default")
      (node (ref "C6") (pin "1") (pinfunction "1_1") (pintype "passive"))
      (node (ref "U2") (pin "60") (pinfunction "AVDD_60") (pintype "bidirectional"))
    )
    (net (code "37") (name "Net-(U2-XTAL1)") (class "Default")
      (node (ref "C2") (pin "1") (pinfunction "1_1") (pintype "passive"))
      (node (ref "U2") (pin "57") (pinfunction "XTAL1_57") (pintype "bidirectional"))
      (node (ref "Y2") (pin "3") (pinfunction "2_3") (pintype "passive"))
    )
    (net (code "38") (name "Net-(U2-XTAL2)") (class "Default")
      (node (ref "C1") (pin "1") (pinfunction "1_1") (pintype "passive"))
      (node (ref "U2") (pin "56") (pinfunction "XTAL2_56") (pintype "bidirectional"))
      (node (ref "Y2") (pin "1") (pinfunction "1_1") (pintype "passive"))
    )
    (net (code "39") (name "PB4") (class "Default")
      (node (ref "U2") (pin "40") (pinfunction "PB4(OC2A/PCINT4)_40") (pintype "bidirectional"))
    )
    (net (code "40") (name "PB5") (class "Default")
      (node (ref "J2") (pin "6") (pinfunction "6_6") (pintype "passive"))
      (node (ref "R5") (pin "1") (pinfunction "1_1") (pintype "passive"))
      (node (ref "U2") (pin "41") (pinfunction "PB5(OC1A/PCINT5)_41") (pintype "bidirectional"))
    )
    (net (code "41") (name "PB6") (class "Default")
      (node (ref "U2") (pin "42") (pinfunction "PB6(OC1B/PCINT6)_42") (pintype "bidirectional"))
    )
    (net (code "42") (name "PB7") (class "Default")
      (node (ref "U2") (pin "43") (pinfunction "PB7(OC0A/OC1C/PCINT7)_43") (pintype "bidirectional"))
    )
    (net (code "43") (name "PD4") (class "Default")
      (node (ref "U2") (pin "29") (pinfunction "PD4(ICP1)_29") (pintype "bidirectional"))
    )
    (net (code "44") (name "PD5") (class "Default")
      (node (ref "U2") (pin "30") (pinfunction "PD5(XCK1)_30") (pintype "bidirectional"))
    )
    (net (code "45") (name "PD6") (class "Default")
      (node (ref "U2") (pin "31") (pinfunction "PD6(T1)_31") (pintype "bidirectional"))
    )
    (net (code "46") (name "PD7") (class "Default")
      (node (ref "U2") (pin "32") (pinfunction "PD7(T0)_32") (pintype "bidirectional"))
    )
    (net (code "47") (name "PE2") (class "Default")
      (node (ref "U2") (pin "48") (pinfunction "PE2(XCK0/AIN0)_48") (pintype "bidirectional"))
    )
    (net (code "48") (name "PE3") (class "Default")
      (node (ref "J2") (pin "3") (pinfunction "3_3") (pintype "passive"))
      (node (ref "R4") (pin "1") (pinfunction "1_1") (pintype "passive"))
      (node (ref "U2") (pin "49") (pinfunction "PE3(OC3A/AIN1)_49") (pintype "bidirectional"))
    )
    (net (code "49") (name "PE4") (class "Default")
      (node (ref "J2") (pin "5") (pinfunction "5_5") (pintype "passive"))
      (node (ref "R6") (pin "1") (pinfunction "1_1") (pintype "passive"))
      (node (ref "U2") (pin "50") (pinfunction "PE4(OC3B/INT4)_50") (pintype "bidirectional"))
    )
    (net (code "50") (name "PE5") (class "Default")
      (node (ref "J2") (pin "4") (pinfunction "4_4") (pintype "passive"))
      (node (ref "R9") (pin "1") (pinfunction "1_1") (pintype "passive"))
      (node (ref "U2") (pin "51") (pinfunction "PE5(OC3C/INT5)_51") (pintype "bidirectional"))
    )
    (net (code "51") (name "PE6") (class "Default")
      (node (ref "U2") (pin "52") (pinfunction "PE6(T3/INT6)_52") (pintype "bidirectional"))
    )
    (net (code "52") (name "PE7") (class "Default")
      (node (ref "U2") (pin "53") (pinfunction "PE7(ICP3/INT7/CLKO)_53") (pintype "bidirectional"))
    )
    (net (code "53") (name "PG0") (class "Default")
      (node (ref "U2") (pin "14") (pinfunction "PG0(DIG3)_14") (pintype "bidirectional"))
    )
    (net (code "54") (name "PG1") (class "Default")
      (node (ref "U2") (pin "15") (pinfunction "PG1(DIG1)_15") (pintype "bidirectional"))
    )
    (net (code "55") (name "PG2") (class "Default")
      (node (ref "U2") (pin "16") (pinfunction "PG2(AMR)_16") (pintype "bidirectional"))
    )
    (net (code "56") (name "PG5") (class "Default")
      (node (ref "U2") (pin "19") (pinfunction "PG5(OC0B)_19") (pintype "bidirectional"))
    )
    (net (code "57") (name "RESET") (class "Default")
      (node (ref "C12") (pin "2") (pinfunction "2_2") (pintype "passive"))
      (node (ref "J1") (pin "5") (pinfunction "5_5") (pintype "passive"))
      (node (ref "R1") (pin "1") (pinfunction "1_1") (pintype "passive"))
      (node (ref "SW1") (pin "3") (pinfunction "2_3") (pintype "passive"))
      (node (ref "SW1") (pin "4") (pinfunction "2_4") (pintype "passive"))
      (node (ref "U2") (pin "12") (pinfunction "RSTN_12") (pintype "bidirectional"))
    )
    (net (code "58") (name "RSTON") (class "Default")
      (node (ref "U2") (pin "13") (pinfunction "RSTON_13") (pintype "bidirectional"))
    )
    (net (code "59") (name "RX1") (class "Default")
      (node (ref "JP4") (pin "TXO") (pinfunction "3_TXO") (pintype "passive"))
      (node (ref "U2") (pin "27") (pinfunction "PD2(RXD1/INT2)_27") (pintype "bidirectional"))
    )
    (net (code "60") (name "RXD1") (class "Default")
      (node (ref "JP3") (pin "TXO") (pinfunction "3_TXO") (pintype "passive"))
      (node (ref "U2") (pin "46") (pinfunction "PE0(RXD0/PCINT8)_46") (pintype "bidirectional"))
    )
    (net (code "61") (name "SCK") (class "Default")
      (node (ref "J1") (pin "3") (pinfunction "3_3") (pintype "passive"))
      (node (ref "U2") (pin "37") (pinfunction "PB1(SCK/PCINT1)_37") (pintype "bidirectional"))
    )
    (net (code "62") (name "SCL") (class "Default")
      (node (ref "J2") (pin "1") (pinfunction "1_1") (pintype "passive"))
      (node (ref "R2") (pin "2") (pinfunction "2_2") (pintype "passive"))
      (node (ref "U$1") (pin "P$2") (pinfunction "P$2.SCL/SCP_P$2") (pintype "bidirectional"))
      (node (ref "U2") (pin "25") (pinfunction "PD0(SCL/INT0)_25") (pintype "bidirectional"))
    )
    (net (code "63") (name "SDA") (class "Default")
      (node (ref "J2") (pin "2") (pinfunction "2_2") (pintype "passive"))
      (node (ref "R7") (pin "2") (pinfunction "2_2") (pintype "passive"))
      (node (ref "U$1") (pin "P$4") (pinfunction "P$4.SDA/SDI/SDO_P$4") (pintype "bidirectional"))
      (node (ref "U2") (pin "26") (pinfunction "PD1(SDA/INT1)_26") (pintype "bidirectional"))
    )
    (net (code "64") (name "SSN") (class "Default")
      (node (ref "U2") (pin "36") (pinfunction "PB0(SSN/PCINT0)_36") (pintype "bidirectional"))
    )
    (net (code "65") (name "TX1") (class "Default")
      (node (ref "JP4") (pin "RXI") (pinfunction "2_RXI") (pintype "passive"))
      (node (ref "U2") (pin "28") (pinfunction "PD3(TXD1/INT3)_28") (pintype "bidirectional"))
    )
    (net (code "66") (name "TXD1") (class "Default")
      (node (ref "JP3") (pin "RXI") (pinfunction "2_RXI") (pintype "passive"))
      (node (ref "U2") (pin "47") (pinfunction "PE1(TXD0)_47") (pintype "bidirectional"))
    )
    (net (code "67") (name "unconnected-(J1-Pad2)") (class "Default")
      (node (ref "J1") (pin "2") (pinfunction "2_2") (pintype "passive"))
    )
    (net (code "68") (name "unconnected-(JP3-4-PadVCC)") (class "Default")
      (node (ref "JP3") (pin "VCC") (pinfunction "4_VCC") (pintype "passive"))
    )
    (net (code "69") (name "unconnected-(JP3-5-PadCTS)") (class "Default")
      (node (ref "JP3") (pin "CTS") (pinfunction "5_CTS") (pintype "passive"))
    )
    (net (code "70") (name "unconnected-(JP4-1-PadDTR)") (class "Default")
      (node (ref "JP4") (pin "DTR") (pinfunction "1_DTR") (pintype "passive"))
    )
    (net (code "71") (name "unconnected-(JP4-4-PadVCC)") (class "Default")
      (node (ref "JP4") (pin "VCC") (pinfunction "4_VCC") (pintype "passive"))
    )
    (net (code "72") (name "unconnected-(JP4-5-PadCTS)") (class "Default")
      (node (ref "JP4") (pin "CTS") (pinfunction "5_CTS") (pintype "passive"))
    )
    (net (code "73") (name "unconnected-(U$1-P$9.DRDY_M-PadP$9)") (class "Default")
      (node (ref "U$1") (pin "P$9") (pinfunction "P$9.DRDY_M_P$9") (pintype "bidirectional"))
    )
    (net (code "74") (name "unconnected-(U$1-P$10.INT_M-PadP$10)") (class "Default")
      (node (ref "U$1") (pin "P$10") (pinfunction "P$10.INT_M_P$10") (pintype "bidirectional"))
    )
    (net (code "75") (name "unconnected-(U$1-P$11.INT1_A{slash}G-PadP$11)") (class "Default")
      (node (ref "U$1") (pin "P$11") (pinfunction "P$11.INT1_A/G_P$11") (pintype "bidirectional"))
    )
    (net (code "76") (name "unconnected-(U$1-P$12.INT2_A{slash}G-PadP$12)") (class "Default")
      (node (ref "U$1") (pin "P$12") (pinfunction "P$12.INT2_A/G_P$12") (pintype "bidirectional"))
    )
  )
)
